# PE01.net
KiCad netlist of a schematic drawn in EAGLE
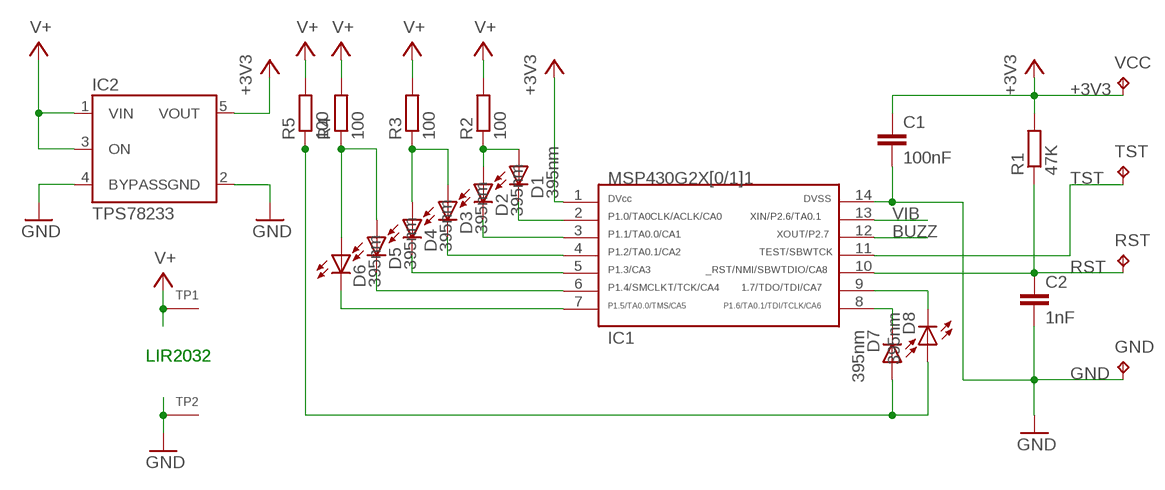
[diagram p0: schematic, sheet 1]

(export (version "E")
  (design (tool "Eeschema 10.0.6"))
  (components
    (comp (ref "C1")
      (value "100nF")
      (footprint "eagle-import:0805")
      (libsource (lib "eagle-import") (part "CAP0805"))
    )
    (comp (ref "C2")
      (value "1nF")
      (footprint "eagle-import:0805")
      (libsource (lib "eagle-import") (part "CAP0805"))
    )
    (comp (ref "D1")
      (value "395nm")
      (footprint "eagle-import:LED-3MM")
      (libsource (lib "eagle-import") (part "LED-3MM"))
    )
    (comp (ref "D2")
      (value "395nm")
      (footprint "eagle-import:LED-3MM")
      (libsource (lib "eagle-import") (part "LED-3MM"))
    )
    (comp (ref "D3")
      (value "395nm")
      (footprint "eagle-import:LED-3MM")
      (libsource (lib "eagle-import") (part "LED-3MM"))
    )
    (comp (ref "D4")
      (value "395nm")
      (footprint "eagle-import:LED-3MM")
      (libsource (lib "eagle-import") (part "LED-3MM"))
    )
    (comp (ref "D5")
      (value "395nm")
      (footprint "eagle-import:LED-3MM")
      (libsource (lib "eagle-import") (part "LED-3MM"))
    )
    (comp (ref "D6")
      (value "395nm")
      (footprint "eagle-import:LED-3MM")
      (libsource (lib "eagle-import") (part "LED-3MM"))
    )
    (comp (ref "D7")
      (value "395nm")
      (footprint "eagle-import:LED-3MM")
      (libsource (lib "eagle-import") (part "LED-3MM"))
    )
    (comp (ref "D8")
      (value "395nm")
      (footprint "eagle-import:LED-3MM")
      (libsource (lib "eagle-import") (part "LED-3MM"))
    )
    (comp (ref "GND")
      (value "TPTP10R")
      (footprint "eagle-import:TP10R")
      (libsource (lib "eagle-import") (part "TPTP10R"))
    )
    (comp (ref "IC1")
      (value "MSP430G2231")
      (footprint "eagle-import:PW14")
      (libsource (lib "eagle-import") (part "G2X[0/1]1---PW14"))
    )
    (comp (ref "IC2")
      (value "TPS78233")
      (footprint "eagle-import:SOT23-5")
      (libsource (lib "eagle-import") (part "LP2982M5"))
    )
    (comp (ref "R1")
      (value "47K")
      (footprint "eagle-import:R0603")
      (libsource (lib "eagle-import") (part "R-EU_R0603"))
    )
    (comp (ref "R2")
      (value "100")
      (footprint "eagle-import:R0603")
      (libsource (lib "eagle-import") (part "R-EU_R0603"))
    )
    (comp (ref "R3")
      (value "100")
      (footprint "eagle-import:R0603")
      (libsource (lib "eagle-import") (part "R-EU_R0603"))
    )
    (comp (ref "R4")
      (value "100")
      (footprint "eagle-import:R0603")
      (libsource (lib "eagle-import") (part "R-EU_R0603"))
    )
    (comp (ref "R5")
      (value "100")
      (footprint "eagle-import:R0603")
      (libsource (lib "eagle-import") (part "R-EU_R0603"))
    )
    (comp (ref "RST")
      (value "TPTP10R")
      (footprint "eagle-import:TP10R")
      (libsource (lib "eagle-import") (part "TPTP10R"))
    )
    (comp (ref "TP1")
      (value "SEWTAP0.4IN")
      (footprint "eagle-import:SEWINGTAP_0.4")
      (libsource (lib "eagle-import") (part "SEWTAP0.4IN"))
    )
    (comp (ref "TP2")
      (value "SEWTAP0.4IN")
      (footprint "eagle-import:SEWINGTAP_0.4")
      (libsource (lib "eagle-import") (part "SEWTAP0.4IN"))
    )
    (comp (ref "TST")
      (value "TPTP10R")
      (footprint "eagle-import:TP10R")
      (libsource (lib "eagle-import") (part "TPTP10R"))
    )
    (comp (ref "VCC")
      (value "TPTP10R")
      (footprint "eagle-import:TP10R")
      (libsource (lib "eagle-import") (part "TPTP10R"))
    )
  )
  (nets
    (net (code "1") (name "+3V3") (class "Default")
      (node (ref "C1") (pin "1") (pinfunction "1_1") (pintype "passive"))
      (node (ref "IC1") (pin "1") (pinfunction "1_1") (pintype "bidirectional"))
      (node (ref "IC2") (pin "5") (pinfunction "VOUT_5") (pintype "output"))
      (node (ref "R1") (pin "2") (pinfunction "2_2") (pintype "passive"))
      (node (ref "VCC") (pin "TP") (pinfunction "TP_TP") (pintype "input"))
    )
    (net (code "2") (name "/BUZZ") (class "Default")
      (node (ref "IC1") (pin "12") (pinfunction "12_12") (pintype "bidirectional"))
    )
    (net (code "3") (name "/RST") (class "Default")
      (node (ref "C2") (pin "1") (pinfunction "1_1") (pintype "passive"))
      (node (ref "IC1") (pin "10") (pinfunction "10_10") (pintype "bidirectional"))
      (node (ref "R1") (pin "1") (pinfunction "1_1") (pintype "passive"))
      (node (ref "RST") (pin "TP") (pinfunction "TP_TP") (pintype "input"))
    )
    (net (code "4") (name "/TST") (class "Default")
      (node (ref "IC1") (pin "11") (pinfunction "11_11") (pintype "bidirectional"))
      (node (ref "TST") (pin "TP") (pinfunction "TP_TP") (pintype "input"))
    )
    (net (code "5") (name "/VIB") (class "Default")
      (node (ref "IC1") (pin "13") (pinfunction "13_13") (pintype "bidirectional"))
    )
    (net (code "6") (name "GND") (class "Default")
      (node (ref "C1") (pin "2") (pinfunction "2_2") (pintype "passive"))
      (node (ref "C2") (pin "2") (pinfunction "2_2") (pintype "passive"))
      (node (ref "GND") (pin "TP") (pinfunction "TP_TP") (pintype "input"))
      (node (ref "IC1") (pin "14") (pinfunction "14_14") (pintype "bidirectional"))
      (node (ref "IC2") (pin "2") (pinfunction "GND_2") (pintype "power_in"))
      (node (ref "IC2") (pin "4") (pinfunction "BYPASS_4") (pintype "passive"))
    )
    (net (code "7") (name "Net-(D1-C)") (class "Default")
      (node (ref "D1") (pin "K") (pinfunction "C_K") (pintype "passive"))
      (node (ref "IC1") (pin "2") (pinfunction "2_2") (pintype "bidirectional"))
    )
    (net (code "8") (name "Net-(D1-PadA)") (class "Default")
      (node (ref "D1") (pin "A") (pinfunction "A_A") (pintype "passive"))
      (node (ref "D2") (pin "A") (pinfunction "A_A") (pintype "passive"))
      (node (ref "R2") (pin "1") (pinfunction "1_1") (pintype "passive"))
    )
    (net (code "9") (name "Net-(D2-C)") (class "Default")
      (node (ref "D2") (pin "K") (pinfunction "C_K") (pintype "passive"))
      (node (ref "IC1") (pin "3") (pinfunction "3_3") (pintype "bidirectional"))
    )
    (net (code "10") (name "Net-(D3-C)") (class "Default")
      (node (ref "D3") (pin "K") (pinfunction "C_K") (pintype "passive"))
      (node (ref "IC1") (pin "4") (pinfunction "4_4") (pintype "bidirectional"))
    )
    (net (code "11") (name "Net-(D3-PadA)") (class "Default")
      (node (ref "D3") (pin "A") (pinfunction "A_A") (pintype "passive"))
      (node (ref "D4") (pin "A") (pinfunction "A_A") (pintype "passive"))
      (node (ref "R3") (pin "1") (pinfunction "1_1") (pintype "passive"))
    )
    (net (code "12") (name "Net-(D4-C)") (class "Default")
      (node (ref "D4") (pin "K") (pinfunction "C_K") (pintype "passive"))
      (node (ref "IC1") (pin "5") (pinfunction "5_5") (pintype "bidirectional"))
    )
    (net (code "13") (name "Net-(D5-C)") (class "Default")
      (node (ref "D5") (pin "K") (pinfunction "C_K") (pintype "passive"))
      (node (ref "IC1") (pin "6") (pinfunction "6_6") (pintype "bidirectional"))
    )
    (net (code "14") (name "Net-(D5-PadA)") (class "Default")
      (node (ref "D5") (pin "A") (pinfunction "A_A") (pintype "passive"))
      (node (ref "D6") (pin "A") (pinfunction "A_A") (pintype "passive"))
      (node (ref "R4") (pin "1") (pinfunction "1_1") (pintype "passive"))
    )
    (net (code "15") (name "Net-(D6-C)") (class "Default")
      (node (ref "D6") (pin "K") (pinfunction "C_K") (pintype "passive"))
      (node (ref "IC1") (pin "7") (pinfunction "7_7") (pintype "bidirectional"))
    )
    (net (code "16") (name "Net-(D7-C)") (class "Default")
      (node (ref "D7") (pin "K") (pinfunction "C_K") (pintype "passive"))
      (node (ref "IC1") (pin "8") (pinfunction "8_8") (pintype "bidirectional"))
    )
    (net (code "17") (name "Net-(D7-PadA)") (class "Default")
      (node (ref "D7") (pin "A") (pinfunction "A_A") (pintype "passive"))
      (node (ref "D8") (pin "A") (pinfunction "A_A") (pintype "passive"))
      (node (ref "R5") (pin "1") (pinfunction "1_1") (pintype "passive"))
    )
    (net (code "18") (name "Net-(D8-C)") (class "Default")
      (node (ref "D8") (pin "K") (pinfunction "C_K") (pintype "passive"))
      (node (ref "IC1") (pin "9") (pinfunction "9_9") (pintype "bidirectional"))
    )
    (net (code "19") (name "V+") (class "Default")
      (node (ref "IC2") (pin "1") (pinfunction "VIN_1") (pintype "power_in"))
      (node (ref "IC2") (pin "3") (pinfunction "ON_3") (pintype "input"))
      (node (ref "R2") (pin "2") (pinfunction "2_2") (pintype "passive"))
      (node (ref "R3") (pin "2") (pinfunction "2_2") (pintype "passive"))
      (node (ref "R4") (pin "2") (pinfunction "2_2") (pintype "passive"))
      (node (ref "R5") (pin "2") (pinfunction "2_2") (pintype "passive"))
    )
    (net (code "20") (name "unconnected-(TP1-SEW-PadTAP)") (class "Default")
      (node (ref "TP1") (pin "TAP") (pinfunction "SEW_TAP") (pintype "bidirectional"))
    )
    (net (code "21") (name "unconnected-(TP2-SEW-PadTAP)") (class "Default")
      (node (ref "TP2") (pin "TAP") (pinfunction "SEW_TAP") (pintype "bidirectional"))
    )
  )
)
